# NB2_DBCON.net
KiCad netlist of a schematic drawn in Altium Designer
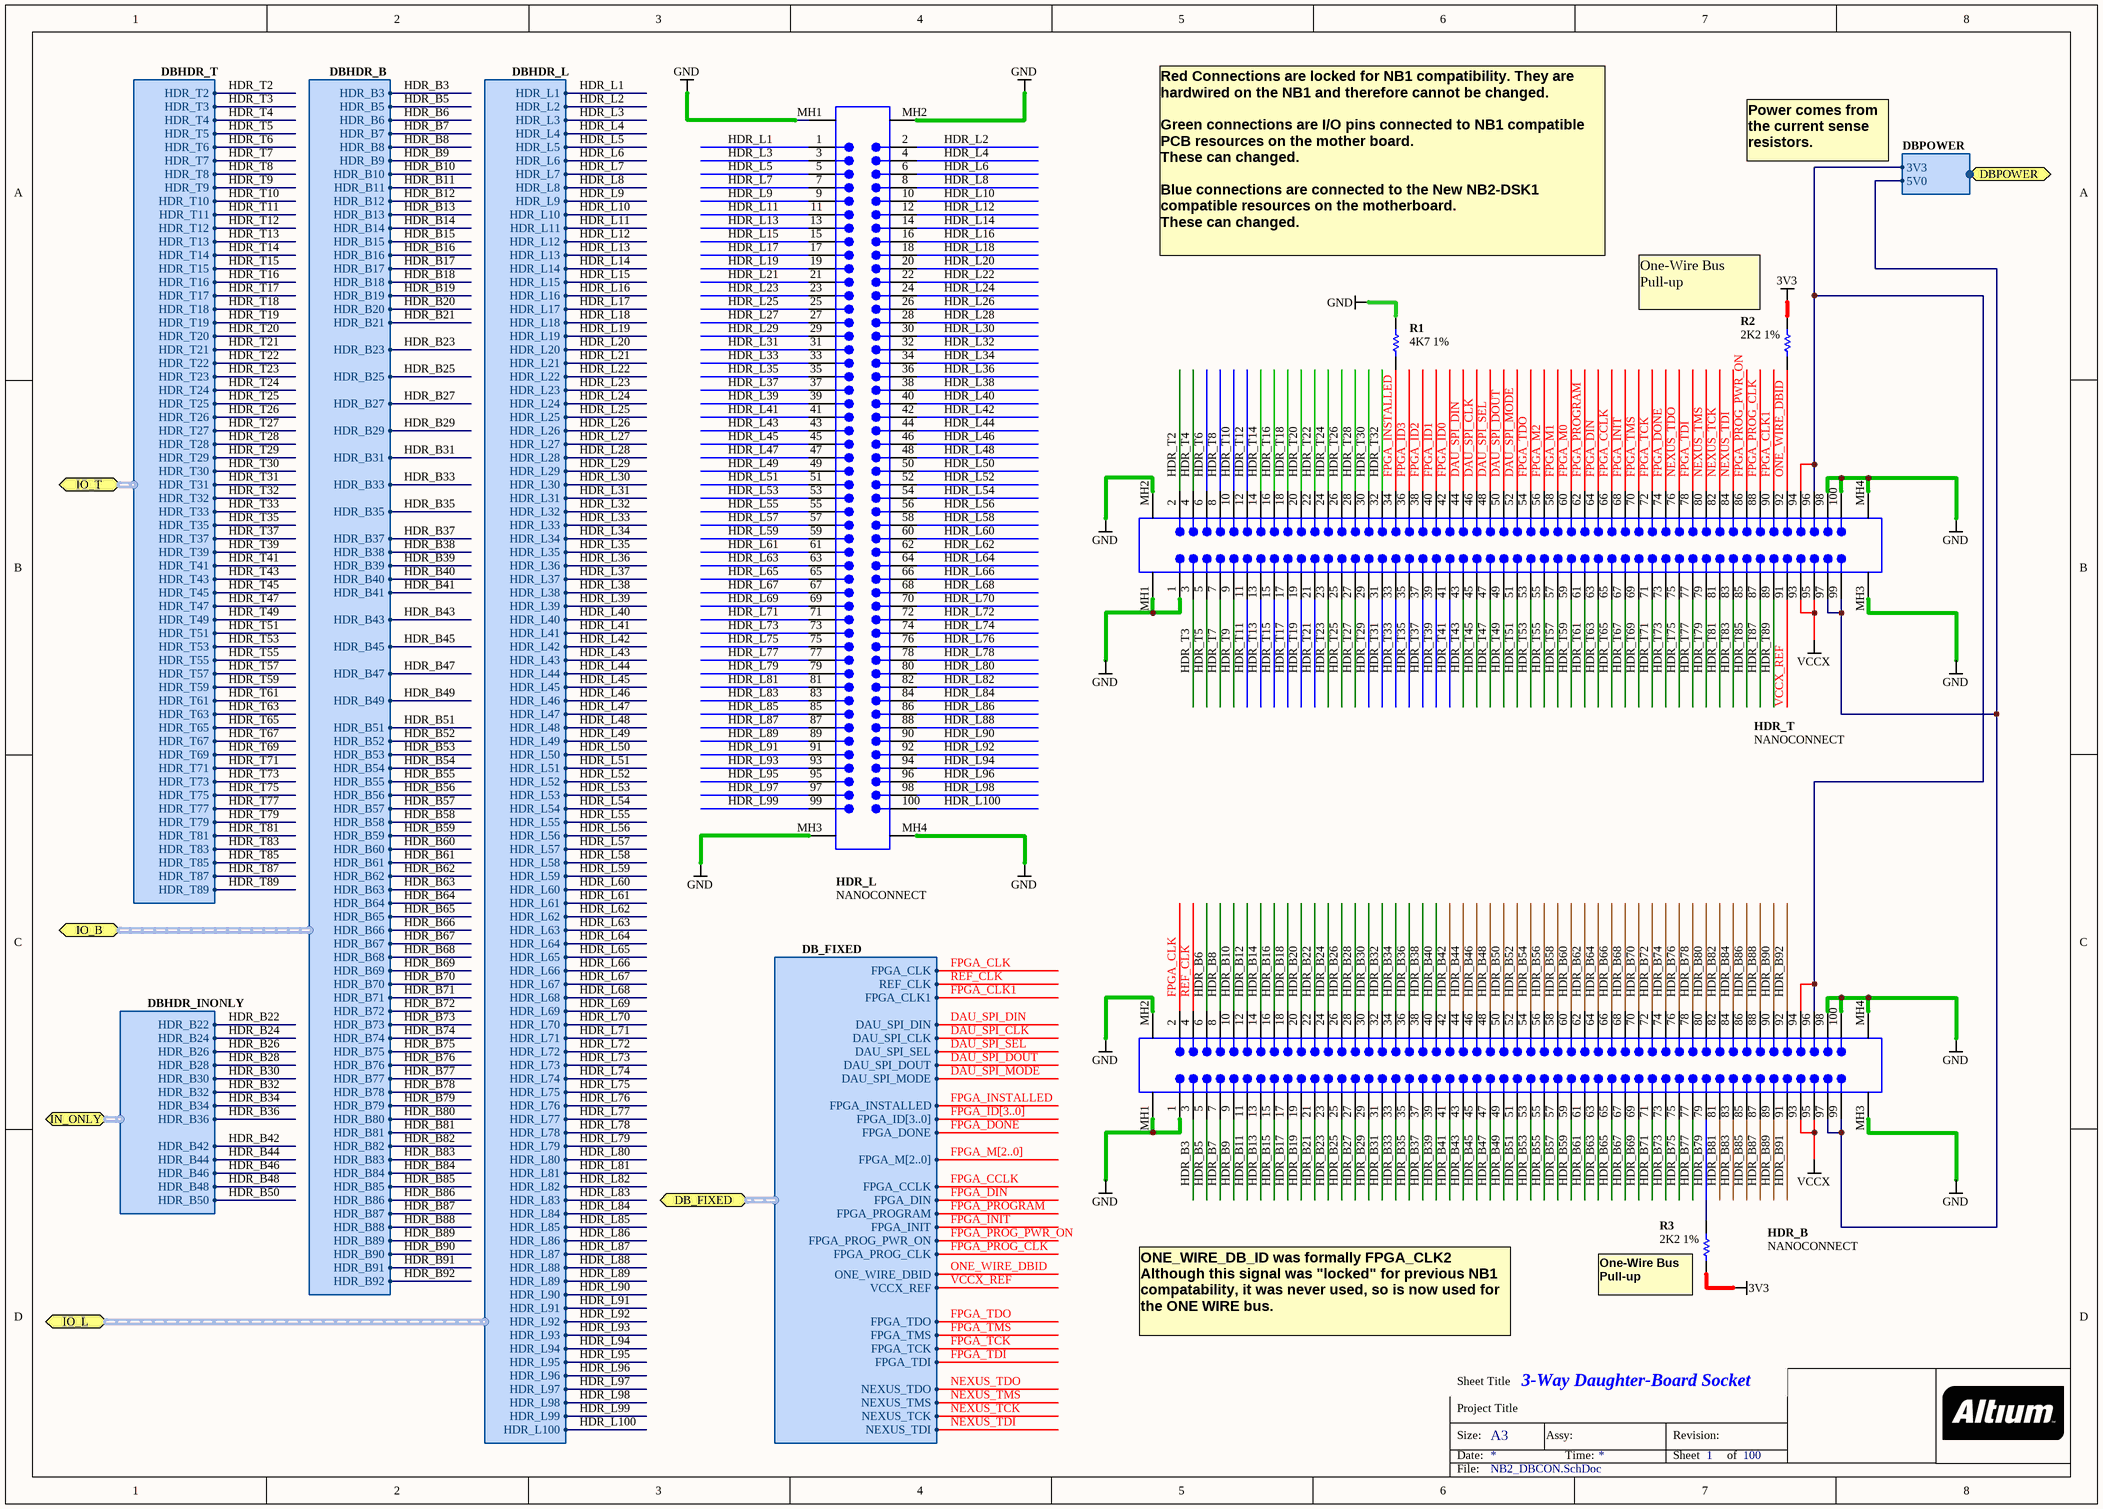
[diagram p0: NB2_DBCON.SchDoc]

(export (version "E")
  (design (tool "Eeschema 10.0.6"))
  (components
    (comp (ref "HDR_B")
      (value "NANOCONNECT")
      (footprint "53751")
      (description "Connector, Molex Docking Station 100 Pin Female 53751")
      (libsource (lib "altium-import") (part "root_1_CON-DOCKSTAT-100-F-STR_"))
    )
    (comp (ref "HDR_L")
      (value "NANOCONNECT")
      (footprint "53751")
      (description "Connector, Molex Docking Station 100 Pin Female 53751")
      (libsource (lib "altium-import") (part "root_0_CON-DOCKSTAT-100-F-STR_"))
    )
    (comp (ref "HDR_T")
      (value "NANOCONNECT")
      (footprint "53751")
      (description "Connector, Molex Docking Station 100 Pin Female 53751")
      (libsource (lib "altium-import") (part "root_1_CON-DOCKSTAT-100-F-STR_"))
    )
    (comp (ref "R1")
      (value "4K7 1%")
      (footprint "RESC1005-STAR")
      (description "Resistor, 4K7 1% 0402 (1005)")
      (fields (field (name "TOLERANCE") "1 %"))
      (libsource (lib "altium-import") (part "root_2_RES_"))
    )
    (comp (ref "R2")
      (value "2K2 1%")
      (footprint "RESC1005-STAR")
      (description "Resistor, 2K2 1% 0402 (1005)")
      (fields (field (name "TOLERANCE") "1 %"))
      (libsource (lib "altium-import") (part "root_2_RES_"))
    )
    (comp (ref "R3")
      (value "2K2 1%")
      (footprint "RESC1005-STAR")
      (description "Resistor, 2K2 1% 0402 (1005)")
      (fields (field (name "TOLERANCE") "1 %"))
      (libsource (lib "altium-import") (part "root_2_RES_"))
    )
  )
  (nets
    (net (code "7") (name "/DAU_SPI_CLK") (class "Default")
      (node (ref "HDR_T") (pin "46") (pinfunction "46_46") (pintype "passive"))
    )
    (net (code "8") (name "/DAU_SPI_DIN") (class "Default")
      (node (ref "HDR_T") (pin "44") (pinfunction "44_44") (pintype "passive"))
    )
    (net (code "9") (name "/DAU_SPI_DOUT") (class "Default")
      (node (ref "HDR_T") (pin "50") (pinfunction "50_50") (pintype "passive"))
    )
    (net (code "10") (name "/DAU_SPI_MODE") (class "Default")
      (node (ref "HDR_T") (pin "52") (pinfunction "52_52") (pintype "passive"))
    )
    (net (code "11") (name "/DAU_SPI_SEL") (class "Default")
      (node (ref "HDR_T") (pin "48") (pinfunction "48_48") (pintype "passive"))
    )
    (net (code "13") (name "/FPGA_CCLK") (class "Default")
      (node (ref "HDR_T") (pin "66") (pinfunction "66_66") (pintype "passive"))
    )
    (net (code "14") (name "/FPGA_CLK") (class "Default")
      (node (ref "HDR_B") (pin "2") (pinfunction "2_2") (pintype "passive"))
    )
    (net (code "15") (name "/FPGA_CLK1") (class "Default")
      (node (ref "HDR_T") (pin "90") (pinfunction "90_90") (pintype "passive"))
    )
    (net (code "16") (name "/FPGA_DIN") (class "Default")
      (node (ref "HDR_T") (pin "64") (pinfunction "64_64") (pintype "passive"))
    )
    (net (code "17") (name "/FPGA_DONE") (class "Default")
      (node (ref "HDR_T") (pin "74") (pinfunction "74_74") (pintype "passive"))
    )
    (net (code "18") (name "/FPGA_ID0") (class "Default")
      (node (ref "HDR_T") (pin "42") (pinfunction "42_42") (pintype "passive"))
    )
    (net (code "19") (name "/FPGA_ID1") (class "Default")
      (node (ref "HDR_T") (pin "40") (pinfunction "40_40") (pintype "passive"))
    )
    (net (code "20") (name "/FPGA_ID2") (class "Default")
      (node (ref "HDR_T") (pin "38") (pinfunction "38_38") (pintype "passive"))
    )
    (net (code "21") (name "/FPGA_ID3") (class "Default")
      (node (ref "HDR_T") (pin "36") (pinfunction "36_36") (pintype "passive"))
    )
    (net (code "23") (name "/FPGA_INIT") (class "Default")
      (node (ref "HDR_T") (pin "68") (pinfunction "68_68") (pintype "passive"))
    )
    (net (code "24") (name "/FPGA_INSTALLED") (class "Default")
      (node (ref "HDR_T") (pin "34") (pinfunction "34_34") (pintype "passive"))
      (node (ref "R1") (pin "1") (pinfunction "1_1") (pintype "passive"))
    )
    (net (code "25") (name "/FPGA_M0") (class "Default")
      (node (ref "HDR_T") (pin "60") (pinfunction "60_60") (pintype "passive"))
    )
    (net (code "26") (name "/FPGA_M1") (class "Default")
      (node (ref "HDR_T") (pin "58") (pinfunction "58_58") (pintype "passive"))
    )
    (net (code "27") (name "/FPGA_M2") (class "Default")
      (node (ref "HDR_T") (pin "56") (pinfunction "56_56") (pintype "passive"))
    )
    (net (code "28") (name "/FPGA_PROGRAM") (class "Default")
      (node (ref "HDR_T") (pin "62") (pinfunction "62_62") (pintype "passive"))
    )
    (net (code "29") (name "/FPGA_PROG_CLK") (class "Default")
      (node (ref "HDR_T") (pin "88") (pinfunction "88_88") (pintype "passive"))
    )
    (net (code "30") (name "/FPGA_PROG_PWR_ON") (class "Default")
      (node (ref "HDR_T") (pin "86") (pinfunction "86_86") (pintype "passive"))
    )
    (net (code "31") (name "/FPGA_TCK") (class "Default")
      (node (ref "HDR_T") (pin "72") (pinfunction "72_72") (pintype "passive"))
    )
    (net (code "32") (name "/FPGA_TDI") (class "Default")
      (node (ref "HDR_T") (pin "78") (pinfunction "78_78") (pintype "passive"))
    )
    (net (code "33") (name "/FPGA_TDO") (class "Default")
      (node (ref "HDR_T") (pin "54") (pinfunction "54_54") (pintype "passive"))
    )
    (net (code "34") (name "/FPGA_TMS") (class "Default")
      (node (ref "HDR_T") (pin "70") (pinfunction "70_70") (pintype "passive"))
    )
    (net (code "35") (name "/HDR_B3") (class "Default")
      (node (ref "HDR_B") (pin "3") (pinfunction "3_3") (pintype "passive"))
    )
    (net (code "36") (name "/HDR_B5") (class "Default")
      (node (ref "HDR_B") (pin "5") (pinfunction "5_5") (pintype "passive"))
    )
    (net (code "37") (name "/HDR_B6") (class "Default")
      (node (ref "HDR_B") (pin "6") (pinfunction "6_6") (pintype "passive"))
    )
    (net (code "38") (name "/HDR_B7") (class "Default")
      (node (ref "HDR_B") (pin "7") (pinfunction "7_7") (pintype "passive"))
    )
    (net (code "39") (name "/HDR_B8") (class "Default")
      (node (ref "HDR_B") (pin "8") (pinfunction "8_8") (pintype "passive"))
    )
    (net (code "40") (name "/HDR_B9") (class "Default")
      (node (ref "HDR_B") (pin "9") (pinfunction "9_9") (pintype "passive"))
    )
    (net (code "41") (name "/HDR_B10") (class "Default")
      (node (ref "HDR_B") (pin "10") (pinfunction "10_10") (pintype "passive"))
    )
    (net (code "42") (name "/HDR_B11") (class "Default")
      (node (ref "HDR_B") (pin "11") (pinfunction "11_11") (pintype "passive"))
    )
    (net (code "43") (name "/HDR_B12") (class "Default")
      (node (ref "HDR_B") (pin "12") (pinfunction "12_12") (pintype "passive"))
    )
    (net (code "44") (name "/HDR_B13") (class "Default")
      (node (ref "HDR_B") (pin "13") (pinfunction "13_13") (pintype "passive"))
    )
    (net (code "45") (name "/HDR_B14") (class "Default")
      (node (ref "HDR_B") (pin "14") (pinfunction "14_14") (pintype "passive"))
    )
    (net (code "46") (name "/HDR_B15") (class "Default")
      (node (ref "HDR_B") (pin "15") (pinfunction "15_15") (pintype "passive"))
    )
    (net (code "47") (name "/HDR_B16") (class "Default")
      (node (ref "HDR_B") (pin "16") (pinfunction "16_16") (pintype "passive"))
    )
    (net (code "48") (name "/HDR_B17") (class "Default")
      (node (ref "HDR_B") (pin "17") (pinfunction "17_17") (pintype "passive"))
    )
    (net (code "49") (name "/HDR_B18") (class "Default")
      (node (ref "HDR_B") (pin "18") (pinfunction "18_18") (pintype "passive"))
    )
    (net (code "50") (name "/HDR_B19") (class "Default")
      (node (ref "HDR_B") (pin "19") (pinfunction "19_19") (pintype "passive"))
    )
    (net (code "51") (name "/HDR_B20") (class "Default")
      (node (ref "HDR_B") (pin "20") (pinfunction "20_20") (pintype "passive"))
    )
    (net (code "52") (name "/HDR_B21") (class "Default")
      (node (ref "HDR_B") (pin "21") (pinfunction "21_21") (pintype "passive"))
    )
    (net (code "53") (name "/HDR_B22") (class "Default")
      (node (ref "HDR_B") (pin "22") (pinfunction "22_22") (pintype "passive"))
    )
    (net (code "54") (name "/HDR_B23") (class "Default")
      (node (ref "HDR_B") (pin "23") (pinfunction "23_23") (pintype "passive"))
    )
    (net (code "55") (name "/HDR_B24") (class "Default")
      (node (ref "HDR_B") (pin "24") (pinfunction "24_24") (pintype "passive"))
    )
    (net (code "56") (name "/HDR_B25") (class "Default")
      (node (ref "HDR_B") (pin "25") (pinfunction "25_25") (pintype "passive"))
    )
    (net (code "57") (name "/HDR_B26") (class "Default")
      (node (ref "HDR_B") (pin "26") (pinfunction "26_26") (pintype "passive"))
    )
    (net (code "58") (name "/HDR_B27") (class "Default")
      (node (ref "HDR_B") (pin "27") (pinfunction "27_27") (pintype "passive"))
    )
    (net (code "59") (name "/HDR_B28") (class "Default")
      (node (ref "HDR_B") (pin "28") (pinfunction "28_28") (pintype "passive"))
    )
    (net (code "60") (name "/HDR_B29") (class "Default")
      (node (ref "HDR_B") (pin "29") (pinfunction "29_29") (pintype "passive"))
    )
    (net (code "61") (name "/HDR_B30") (class "Default")
      (node (ref "HDR_B") (pin "30") (pinfunction "30_30") (pintype "passive"))
    )
    (net (code "62") (name "/HDR_B31") (class "Default")
      (node (ref "HDR_B") (pin "31") (pinfunction "31_31") (pintype "passive"))
    )
    (net (code "63") (name "/HDR_B32") (class "Default")
      (node (ref "HDR_B") (pin "32") (pinfunction "32_32") (pintype "passive"))
    )
    (net (code "64") (name "/HDR_B33") (class "Default")
      (node (ref "HDR_B") (pin "33") (pinfunction "33_33") (pintype "passive"))
    )
    (net (code "65") (name "/HDR_B34") (class "Default")
      (node (ref "HDR_B") (pin "34") (pinfunction "34_34") (pintype "passive"))
    )
    (net (code "66") (name "/HDR_B35") (class "Default")
      (node (ref "HDR_B") (pin "35") (pinfunction "35_35") (pintype "passive"))
    )
    (net (code "67") (name "/HDR_B36") (class "Default")
      (node (ref "HDR_B") (pin "36") (pinfunction "36_36") (pintype "passive"))
    )
    (net (code "68") (name "/HDR_B37") (class "Default")
      (node (ref "HDR_B") (pin "37") (pinfunction "37_37") (pintype "passive"))
    )
    (net (code "69") (name "/HDR_B38") (class "Default")
      (node (ref "HDR_B") (pin "38") (pinfunction "38_38") (pintype "passive"))
    )
    (net (code "70") (name "/HDR_B39") (class "Default")
      (node (ref "HDR_B") (pin "39") (pinfunction "39_39") (pintype "passive"))
    )
    (net (code "71") (name "/HDR_B40") (class "Default")
      (node (ref "HDR_B") (pin "40") (pinfunction "40_40") (pintype "passive"))
    )
    (net (code "72") (name "/HDR_B41") (class "Default")
      (node (ref "HDR_B") (pin "41") (pinfunction "41_41") (pintype "passive"))
    )
    (net (code "73") (name "/HDR_B42") (class "Default")
      (node (ref "HDR_B") (pin "42") (pinfunction "42_42") (pintype "passive"))
    )
    (net (code "74") (name "/HDR_B43") (class "Default")
      (node (ref "HDR_B") (pin "43") (pinfunction "43_43") (pintype "passive"))
    )
    (net (code "75") (name "/HDR_B44") (class "Default")
      (node (ref "HDR_B") (pin "44") (pinfunction "44_44") (pintype "passive"))
    )
    (net (code "76") (name "/HDR_B45") (class "Default")
      (node (ref "HDR_B") (pin "45") (pinfunction "45_45") (pintype "passive"))
    )
    (net (code "77") (name "/HDR_B46") (class "Default")
      (node (ref "HDR_B") (pin "46") (pinfunction "46_46") (pintype "passive"))
    )
    (net (code "78") (name "/HDR_B47") (class "Default")
      (node (ref "HDR_B") (pin "47") (pinfunction "47_47") (pintype "passive"))
    )
    (net (code "79") (name "/HDR_B48") (class "Default")
      (node (ref "HDR_B") (pin "48") (pinfunction "48_48") (pintype "passive"))
    )
    (net (code "80") (name "/HDR_B49") (class "Default")
      (node (ref "HDR_B") (pin "49") (pinfunction "49_49") (pintype "passive"))
    )
    (net (code "81") (name "/HDR_B50") (class "Default")
      (node (ref "HDR_B") (pin "50") (pinfunction "50_50") (pintype "passive"))
    )
    (net (code "82") (name "/HDR_B51") (class "Default")
      (node (ref "HDR_B") (pin "51") (pinfunction "51_51") (pintype "passive"))
    )
    (net (code "83") (name "/HDR_B52") (class "Default")
      (node (ref "HDR_B") (pin "52") (pinfunction "52_52") (pintype "passive"))
    )
    (net (code "84") (name "/HDR_B53") (class "Default")
      (node (ref "HDR_B") (pin "53") (pinfunction "53_53") (pintype "passive"))
    )
    (net (code "85") (name "/HDR_B54") (class "Default")
      (node (ref "HDR_B") (pin "54") (pinfunction "54_54") (pintype "passive"))
    )
    (net (code "86") (name "/HDR_B55") (class "Default")
      (node (ref "HDR_B") (pin "55") (pinfunction "55_55") (pintype "passive"))
    )
    (net (code "87") (name "/HDR_B56") (class "Default")
      (node (ref "HDR_B") (pin "56") (pinfunction "56_56") (pintype "passive"))
    )
    (net (code "88") (name "/HDR_B57") (class "Default")
      (node (ref "HDR_B") (pin "57") (pinfunction "57_57") (pintype "passive"))
    )
    (net (code "89") (name "/HDR_B58") (class "Default")
      (node (ref "HDR_B") (pin "58") (pinfunction "58_58") (pintype "passive"))
    )
    (net (code "90") (name "/HDR_B59") (class "Default")
      (node (ref "HDR_B") (pin "59") (pinfunction "59_59") (pintype "passive"))
    )
    (net (code "91") (name "/HDR_B60") (class "Default")
      (node (ref "HDR_B") (pin "60") (pinfunction "60_60") (pintype "passive"))
    )
    (net (code "92") (name "/HDR_B61") (class "Default")
      (node (ref "HDR_B") (pin "61") (pinfunction "61_61") (pintype "passive"))
    )
    (net (code "93") (name "/HDR_B62") (class "Default")
      (node (ref "HDR_B") (pin "62") (pinfunction "62_62") (pintype "passive"))
    )
    (net (code "94") (name "/HDR_B63") (class "Default")
      (node (ref "HDR_B") (pin "63") (pinfunction "63_63") (pintype "passive"))
    )
    (net (code "95") (name "/HDR_B64") (class "Default")
      (node (ref "HDR_B") (pin "64") (pinfunction "64_64") (pintype "passive"))
    )
    (net (code "96") (name "/HDR_B65") (class "Default")
      (node (ref "HDR_B") (pin "65") (pinfunction "65_65") (pintype "passive"))
    )
    (net (code "97") (name "/HDR_B66") (class "Default")
      (node (ref "HDR_B") (pin "66") (pinfunction "66_66") (pintype "passive"))
    )
    (net (code "98") (name "/HDR_B67") (class "Default")
      (node (ref "HDR_B") (pin "67") (pinfunction "67_67") (pintype "passive"))
    )
    (net (code "99") (name "/HDR_B68") (class "Default")
      (node (ref "HDR_B") (pin "68") (pinfunction "68_68") (pintype "passive"))
    )
    (net (code "100") (name "/HDR_B69") (class "Default")
      (node (ref "HDR_B") (pin "69") (pinfunction "69_69") (pintype "passive"))
    )
    (net (code "101") (name "/HDR_B70") (class "Default")
      (node (ref "HDR_B") (pin "70") (pinfunction "70_70") (pintype "passive"))
    )
    (net (code "102") (name "/HDR_B71") (class "Default")
      (node (ref "HDR_B") (pin "71") (pinfunction "71_71") (pintype "passive"))
    )
    (net (code "103") (name "/HDR_B72") (class "Default")
      (node (ref "HDR_B") (pin "72") (pinfunction "72_72") (pintype "passive"))
    )
    (net (code "104") (name "/HDR_B73") (class "Default")
      (node (ref "HDR_B") (pin "73") (pinfunction "73_73") (pintype "passive"))
    )
    (net (code "105") (name "/HDR_B74") (class "Default")
      (node (ref "HDR_B") (pin "74") (pinfunction "74_74") (pintype "passive"))
    )
    (net (code "106") (name "/HDR_B75") (class "Default")
      (node (ref "HDR_B") (pin "75") (pinfunction "75_75") (pintype "passive"))
    )
    (net (code "107") (name "/HDR_B76") (class "Default")
      (node (ref "HDR_B") (pin "76") (pinfunction "76_76") (pintype "passive"))
    )
    (net (code "108") (name "/HDR_B77") (class "Default")
      (node (ref "HDR_B") (pin "77") (pinfunction "77_77") (pintype "passive"))
    )
    (net (code "109") (name "/HDR_B78") (class "Default")
      (node (ref "HDR_B") (pin "78") (pinfunction "78_78") (pintype "passive"))
    )
    (net (code "110") (name "/HDR_B79") (class "Default")
      (node (ref "HDR_B") (pin "79") (pinfunction "79_79") (pintype "passive"))
      (node (ref "R3") (pin "2") (pinfunction "2_2") (pintype "passive"))
    )
    (net (code "111") (name "/HDR_B80") (class "Default")
      (node (ref "HDR_B") (pin "80") (pinfunction "80_80") (pintype "passive"))
    )
    (net (code "112") (name "/HDR_B81") (class "Default")
      (node (ref "HDR_B") (pin "81") (pinfunction "81_81") (pintype "passive"))
    )
    (net (code "113") (name "/HDR_B82") (class "Default")
      (node (ref "HDR_B") (pin "82") (pinfunction "82_82") (pintype "passive"))
    )
    (net (code "114") (name "/HDR_B83") (class "Default")
      (node (ref "HDR_B") (pin "83") (pinfunction "83_83") (pintype "passive"))
    )
    (net (code "115") (name "/HDR_B84") (class "Default")
      (node (ref "HDR_B") (pin "84") (pinfunction "84_84") (pintype "passive"))
    )
    (net (code "116") (name "/HDR_B85") (class "Default")
      (node (ref "HDR_B") (pin "85") (pinfunction "85_85") (pintype "passive"))
    )
    (net (code "117") (name "/HDR_B86") (class "Default")
      (node (ref "HDR_B") (pin "86") (pinfunction "86_86") (pintype "passive"))
    )
    (net (code "118") (name "/HDR_B87") (class "Default")
      (node (ref "HDR_B") (pin "87") (pinfunction "87_87") (pintype "passive"))
    )
    (net (code "119") (name "/HDR_B88") (class "Default")
      (node (ref "HDR_B") (pin "88") (pinfunction "88_88") (pintype "passive"))
    )
    (net (code "120") (name "/HDR_B89") (class "Default")
      (node (ref "HDR_B") (pin "89") (pinfunction "89_89") (pintype "passive"))
    )
    (net (code "121") (name "/HDR_B90") (class "Default")
      (node (ref "HDR_B") (pin "90") (pinfunction "90_90") (pintype "passive"))
    )
    (net (code "122") (name "/HDR_B91") (class "Default")
      (node (ref "HDR_B") (pin "91") (pinfunction "91_91") (pintype "passive"))
    )
    (net (code "123") (name "/HDR_B92") (class "Default")
      (node (ref "HDR_B") (pin "92") (pinfunction "92_92") (pintype "passive"))
    )
    (net (code "124") (name "/HDR_L1") (class "Default")
      (node (ref "HDR_L") (pin "1") (pinfunction "1_1") (pintype "passive"))
    )
    (net (code "125") (name "/HDR_L2") (class "Default")
      (node (ref "HDR_L") (pin "2") (pinfunction "2_2") (pintype "passive"))
    )
    (net (code "126") (name "/HDR_L3") (class "Default")
      (node (ref "HDR_L") (pin "3") (pinfunction "3_3") (pintype "passive"))
    )
    (net (code "127") (name "/HDR_L4") (class "Default")
      (node (ref "HDR_L") (pin "4") (pinfunction "4_4") (pintype "passive"))
    )
    (net (code "128") (name "/HDR_L5") (class "Default")
      (node (ref "HDR_L") (pin "5") (pinfunction "5_5") (pintype "passive"))
    )
    (net (code "129") (name "/HDR_L6") (class "Default")
      (node (ref "HDR_L") (pin "6") (pinfunction "6_6") (pintype "passive"))
    )
    (net (code "130") (name "/HDR_L7") (class "Default")
      (node (ref "HDR_L") (pin "7") (pinfunction "7_7") (pintype "passive"))
    )
    (net (code "131") (name "/HDR_L8") (class "Default")
      (node (ref "HDR_L") (pin "8") (pinfunction "8_8") (pintype "passive"))
    )
    (net (code "132") (name "/HDR_L9") (class "Default")
      (node (ref "HDR_L") (pin "9") (pinfunction "9_9") (pintype "passive"))
    )
    (net (code "133") (name "/HDR_L10") (class "Default")
      (node (ref "HDR_L") (pin "10") (pinfunction "10_10") (pintype "passive"))
    )
    (net (code "134") (name "/HDR_L11") (class "Default")
      (node (ref "HDR_L") (pin "11") (pinfunction "11_11") (pintype "passive"))
    )
    (net (code "135") (name "/HDR_L12") (class "Default")
      (node (ref "HDR_L") (pin "12") (pinfunction "12_12") (pintype "passive"))
    )
    (net (code "136") (name "/HDR_L13") (class "Default")
      (node (ref "HDR_L") (pin "13") (pinfunction "13_13") (pintype "passive"))
    )
    (net (code "137") (name "/HDR_L14") (class "Default")
      (node (ref "HDR_L") (pin "14") (pinfunction "14_14") (pintype "passive"))
    )
    (net (code "138") (name "/HDR_L15") (class "Default")
      (node (ref "HDR_L") (pin "15") (pinfunction "15_15") (pintype "passive"))
    )
    (net (code "139") (name "/HDR_L16") (class "Default")
      (node (ref "HDR_L") (pin "16") (pinfunction "16_16") (pintype "passive"))
    )
    (net (code "140") (name "/HDR_L17") (class "Default")
      (node (ref "HDR_L") (pin "17") (pinfunction "17_17") (pintype "passive"))
    )
    (net (code "141") (name "/HDR_L18") (class "Default")
      (node (ref "HDR_L") (pin "18") (pinfunction "18_18") (pintype "passive"))
    )
    (net (code "142") (name "/HDR_L19") (class "Default")
      (node (ref "HDR_L") (pin "19") (pinfunction "19_19") (pintype "passive"))
    )
    (net (code "143") (name "/HDR_L20") (class "Default")
      (node (ref "HDR_L") (pin "20") (pinfunction "20_20") (pintype "passive"))
    )
    (net (code "144") (name "/HDR_L21") (class "Default")
      (node (ref "HDR_L") (pin "21") (pinfunction "21_21") (pintype "passive"))
    )
    (net (code "145") (name "/HDR_L22") (class "Default")
      (node (ref "HDR_L") (pin "22") (pinfunction "22_22") (pintype "passive"))
    )
    (net (code "146") (name "/HDR_L23") (class "Default")
      (node (ref "HDR_L") (pin "23") (pinfunction "23_23") (pintype "passive"))
    )
    (net (code "147") (name "/HDR_L24") (class "Default")
      (node (ref "HDR_L") (pin "24") (pinfunction "24_24") (pintype "passive"))
    )
    (net (code "148") (name "/HDR_L25") (class "Default")
      (node (ref "HDR_L") (pin "25") (pinfunction "25_25") (pintype "passive"))
    )
    (net (code "149") (name "/HDR_L26") (class "Default")
      (node (ref "HDR_L") (pin "26") (pinfunction "26_26") (pintype "passive"))
    )
    (net (code "150") (name "/HDR_L27") (class "Default")
      (node (ref "HDR_L") (pin "27") (pinfunction "27_27") (pintype "passive"))
    )
    (net (code "151") (name "/HDR_L28") (class "Default")
      (node (ref "HDR_L") (pin "28") (pinfunction "28_28") (pintype "passive"))
    )
    (net (code "152") (name "/HDR_L29") (class "Default")
      (node (ref "HDR_L") (pin "29") (pinfunction "29_29") (pintype "passive"))
    )
    (net (code "153") (name "/HDR_L30") (class "Default")
      (node (ref "HDR_L") (pin "30") (pinfunction "30_30") (pintype "passive"))
    )
    (net (code "154") (name "/HDR_L31") (class "Default")
      (node (ref "HDR_L") (pin "31") (pinfunction "31_31") (pintype "passive"))
    )
    (net (code "155") (name "/HDR_L32") (class "Default")
      (node (ref "HDR_L") (pin "32") (pinfunction "32_32") (pintype "passive"))
    )
    (net (code "156") (name "/HDR_L33") (class "Default")
      (node (ref "HDR_L") (pin "33") (pinfunction "33_33") (pintype "passive"))
    )
    (net (code "157") (name "/HDR_L34") (class "Default")
      (node (ref "HDR_L") (pin "34") (pinfunction "34_34") (pintype "passive"))
    )
    (net (code "158") (name "/HDR_L35") (class "Default")
      (node (ref "HDR_L") (pin "35") (pinfunction "35_35") (pintype "passive"))
    )
    (net (code "159") (name "/HDR_L36") (class "Default")
      (node (ref "HDR_L") (pin "36") (pinfunction "36_36") (pintype "passive"))
    )
    (net (code "160") (name "/HDR_L37") (class "Default")
      (node (ref "HDR_L") (pin "37") (pinfunction "37_37") (pintype "passive"))
    )
    (net (code "161") (name "/HDR_L38") (class "Default")
      (node (ref "HDR_L") (pin "38") (pinfunction "38_38") (pintype "passive"))
    )
    (net (code "162") (name "/HDR_L39") (class "Default")
      (node (ref "HDR_L") (pin "39") (pinfunction "39_39") (pintype "passive"))
    )
    (net (code "163") (name "/HDR_L40") (class "Default")
      (node (ref "HDR_L") (pin "40") (pinfunction "40_40") (pintype "passive"))
    )
    (net (code "164") (name "/HDR_L41") (class "Default")
      (node (ref "HDR_L") (pin "41") (pinfunction "41_41") (pintype "passive"))
    )
    (net (code "165") (name "/HDR_L42") (class "Default")
      (node (ref "HDR_L") (pin "42") (pinfunction "42_42") (pintype "passive"))
    )
    (net (code "166") (name "/HDR_L43") (class "Default")
      (node (ref "HDR_L") (pin "43") (pinfunction "43_43") (pintype "passive"))
    )
    (net (code "167") (name "/HDR_L44") (class "Default")
      (node (ref "HDR_L") (pin "44") (pinfunction "44_44") (pintype "passive"))
    )
    (net (code "168") (name "/HDR_L45") (class "Default")
      (node (ref "HDR_L") (pin "45") (pinfunction "45_45") (pintype "passive"))
    )
    (net (code "169") (name "/HDR_L46") (class "Default")
      (node (ref "HDR_L") (pin "46") (pinfunction "46_46") (pintype "passive"))
    )
    (net (code "170") (name "/HDR_L47") (class "Default")
      (node (ref "HDR_L") (pin "47") (pinfunction "47_47") (pintype "passive"))
    )
    (net (code "171") (name "/HDR_L48") (class "Default")
      (node (ref "HDR_L") (pin "48") (pinfunction "48_48") (pintype "passive"))
    )
    (net (code "172") (name "/HDR_L49") (class "Default")
      (node (ref "HDR_L") (pin "49") (pinfunction "49_49") (pintype "passive"))
    )
    (net (code "173") (name "/HDR_L50") (class "Default")
      (node (ref "HDR_L") (pin "50") (pinfunction "50_50") (pintype "passive"))
    )
    (net (code "174") (name "/HDR_L51") (class "Default")
      (node (ref "HDR_L") (pin "51") (pinfunction "51_51") (pintype "passive"))
    )
    (net (code "175") (name "/HDR_L52") (class "Default")
      (node (ref "HDR_L") (pin "52") (pinfunction "52_52") (pintype "passive"))
    )
    (net (code "176") (name "/HDR_L53") (class "Default")
      (node (ref "HDR_L") (pin "53") (pinfunction "53_53") (pintype "passive"))
    )
    (net (code "177") (name "/HDR_L54") (class "Default")
      (node (ref "HDR_L") (pin "54") (pinfunction "54_54") (pintype "passive"))
    )
    (net (code "178") (name "/HDR_L55") (class "Default")
      (node (ref "HDR_L") (pin "55") (pinfunction "55_55") (pintype "passive"))
    )
    (net (code "179") (name "/HDR_L56") (class "Default")
      (node (ref "HDR_L") (pin "56") (pinfunction "56_56") (pintype "passive"))
    )
    (net (code "180") (name "/HDR_L57") (class "Default")
      (node (ref "HDR_L") (pin "57") (pinfunction "57_57") (pintype "passive"))
    )
    (net (code "181") (name "/HDR_L58") (class "Default")
      (node (ref "HDR_L") (pin "58") (pinfunction "58_58") (pintype "passive"))
    )
    (net (code "182") (name "/HDR_L59") (class "Default")
      (node (ref "HDR_L") (pin "59") (pinfunction "59_59") (pintype "passive"))
    )
    (net (code "183") (name "/HDR_L60") (class "Default")
      (node (ref "HDR_L") (pin "60") (pinfunction "60_60") (pintype "passive"))
    )
    (net (code "184") (name "/HDR_L61") (class "Default")
      (node (ref "HDR_L") (pin "61") (pinfunction "61_61") (pintype "passive"))
    )
    (net (code "185") (name "/HDR_L62") (class "Default")
      (node (ref "HDR_L") (pin "62") (pinfunction "62_62") (pintype "passive"))
    )
    (net (code "186") (name "/HDR_L63") (class "Default")
      (node (ref "HDR_L") (pin "63") (pinfunction "63_63") (pintype "passive"))
    )
    (net (code "187") (name "/HDR_L64") (class "Default")
      (node (ref "HDR_L") (pin "64") (pinfunction "64_64") (pintype "passive"))
    )
    (net (code "188") (name "/HDR_L65") (class "Default")
      (node (ref "HDR_L") (pin "65") (pinfunction "65_65") (pintype "passive"))
    )
    (net (code "189") (name "/HDR_L66") (class "Default")
      (node (ref "HDR_L") (pin "66") (pinfunction "66_66") (pintype "passive"))
    )
    (net (code "190") (name "/HDR_L67") (class "Default")
      (node (ref "HDR_L") (pin "67") (pinfunction "67_67") (pintype "passive"))
    )
    (net (code "191") (name "/HDR_L68") (class "Default")
      (node (ref "HDR_L") (pin "68") (pinfunction "68_68") (pintype "passive"))
    )
    (net (code "192") (name "/HDR_L69") (class "Default")
      (node (ref "HDR_L") (pin "69") (pinfunction "69_69") (pintype "passive"))
    )
    (net (code "193") (name "/HDR_L70") (class "Default")
      (node (ref "HDR_L") (pin "70") (pinfunction "70_70") (pintype "passive"))
    )
    (net (code "194") (name "/HDR_L71") (class "Default")
      (node (ref "HDR_L") (pin "71") (pinfunction "71_71") (pintype "passive"))
    )
    (net (code "195") (name "/HDR_L72") (class "Default")
      (node (ref "HDR_L") (pin "72") (pinfunction "72_72") (pintype "passive"))
    )
    (net (code "196") (name "/HDR_L73") (class "Default")
      (node (ref "HDR_L") (pin "73") (pinfunction "73_73") (pintype "passive"))
    )
    (net (code "197") (name "/HDR_L74") (class "Default")
      (node (ref "HDR_L") (pin "74") (pinfunction "74_74") (pintype "passive"))
    )
    (net (code "198") (name "/HDR_L75") (class "Default")
      (node (ref "HDR_L") (pin "75") (pinfunction "75_75") (pintype "passive"))
    )
    (net (code "199") (name "/HDR_L76") (class "Default")
      (node (ref "HDR_L") (pin "76") (pinfunction "76_76") (pintype "passive"))
    )
    (net (code "200") (name "/HDR_L77") (class "Default")
      (node (ref "HDR_L") (pin "77") (pinfunction "77_77") (pintype "passive"))
    )
    (net (code "201") (name "/HDR_L78") (class "Default")
      (node (ref "HDR_L") (pin "78") (pinfunction "78_78") (pintype "passive"))
    )
    (net (code "202") (name "/HDR_L79") (class "Default")
      (node (ref "HDR_L") (pin "79") (pinfunction "79_79") (pintype "passive"))
    )
    (net (code "203") (name "/HDR_L80") (class "Default")
      (node (ref "HDR_L") (pin "80") (pinfunction "80_80") (pintype "passive"))
    )
    (net (code "204") (name "/HDR_L81") (class "Default")
      (node (ref "HDR_L") (pin "81") (pinfunction "81_81") (pintype "passive"))
    )
    (net (code "205") (name "/HDR_L82") (class "Default")
      (node (ref "HDR_L") (pin "82") (pinfunction "82_82") (pintype "passive"))
    )
    (net (code "206") (name "/HDR_L83") (class "Default")
      (node (ref "HDR_L") (pin "83") (pinfunction "83_83") (pintype "passive"))
    )
    (net (code "207") (name "/HDR_L84") (class "Default")
      (node (ref "HDR_L") (pin "84") (pinfunction "84_84") (pintype "passive"))
    )
    (net (code "208") (name "/HDR_L85") (class "Default")
      (node (ref "HDR_L") (pin "85") (pinfunction "85_85") (pintype "passive"))
    )
    (net (code "209") (name "/HDR_L86") (class "Default")
      (node (ref "HDR_L") (pin "86") (pinfunction "86_86") (pintype "passive"))
    )
    (net (code "210") (name "/HDR_L87") (class "Default")
      (node (ref "HDR_L") (pin "87") (pinfunction "87_87") (pintype "passive"))
    )
    (net (code "211") (name "/HDR_L88") (class "Default")
      (node (ref "HDR_L") (pin "88") (pinfunction "88_88") (pintype "passive"))
    )
    (net (code "212") (name "/HDR_L89") (class "Default")
      (node (ref "HDR_L") (pin "89") (pinfunction "89_89") (pintype "passive"))
    )
    (net (code "213") (name "/HDR_L90") (class "Default")
      (node (ref "HDR_L") (pin "90") (pinfunction "90_90") (pintype "passive"))
    )
    (net (code "214") (name "/HDR_L91") (class "Default")
      (node (ref "HDR_L") (pin "91") (pinfunction "91_91") (pintype "passive"))
    )
    (net (code "215") (name "/HDR_L92") (class "Default")
      (node (ref "HDR_L") (pin "92") (pinfunction "92_92") (pintype "passive"))
    )
    (net (code "216") (name "/HDR_L93") (class "Default")
      (node (ref "HDR_L") (pin "93") (pinfunction "93_93") (pintype "passive"))
    )
    (net (code "217") (name "/HDR_L94") (class "Default")
      (node (ref "HDR_L") (pin "94") (pinfunction "94_94") (pintype "passive"))
    )
    (net (code "218") (name "/HDR_L95") (class "Default")
      (node (ref "HDR_L") (pin "95") (pinfunction "95_95") (pintype "passive"))
    )
    (net (code "219") (name "/HDR_L96") (class "Default")
      (node (ref "HDR_L") (pin "96") (pinfunction "96_96") (pintype "passive"))
    )
    (net (code "220") (name "/HDR_L97") (class "Default")
      (node (ref "HDR_L") (pin "97") (pinfunction "97_97") (pintype "passive"))
    )
    (net (code "221") (name "/HDR_L98") (class "Default")
      (node (ref "HDR_L") (pin "98") (pinfunction "98_98") (pintype "passive"))
    )
    (net (code "222") (name "/HDR_L99") (class "Default")
      (node (ref "HDR_L") (pin "99") (pinfunction "99_99") (pintype "passive"))
    )
    (net (code "223") (name "/HDR_L100") (class "Default")
      (node (ref "HDR_L") (pin "100") (pinfunction "100_100") (pintype "passive"))
    )
    (net (code "224") (name "/HDR_T2") (class "Default")
      (node (ref "HDR_T") (pin "2") (pinfunction "2_2") (pintype "passive"))
    )
    (net (code "225") (name "/HDR_T3") (class "Default")
      (node (ref "HDR_T") (pin "3") (pinfunction "3_3") (pintype "passive"))
    )
    (net (code "226") (name "/HDR_T4") (class "Default")
      (node (ref "HDR_T") (pin "4") (pinfunction "4_4") (pintype "passive"))
    )
    (net (code "227") (name "/HDR_T5") (class "Default")
      (node (ref "HDR_T") (pin "5") (pinfunction "5_5") (pintype "passive"))
    )
    (net (code "228") (name "/HDR_T6") (class "Default")
      (node (ref "HDR_T") (pin "6") (pinfunction "6_6") (pintype "passive"))
    )
    (net (code "229") (name "/HDR_T7") (class "Default")
      (node (ref "HDR_T") (pin "7") (pinfunction "7_7") (pintype "passive"))
    )
    (net (code "230") (name "/HDR_T8") (class "Default")
      (node (ref "HDR_T") (pin "8") (pinfunction "8_8") (pintype "passive"))
    )
    (net (code "231") (name "/HDR_T9") (class "Default")
      (node (ref "HDR_T") (pin "9") (pinfunction "9_9") (pintype "passive"))
    )
    (net (code "232") (name "/HDR_T10") (class "Default")
      (node (ref "HDR_T") (pin "10") (pinfunction "10_10") (pintype "passive"))
    )
    (net (code "233") (name "/HDR_T11") (class "Default")
      (node (ref "HDR_T") (pin "11") (pinfunction "11_11") (pintype "passive"))
    )
    (net (code "234") (name "/HDR_T12") (class "Default")
      (node (ref "HDR_T") (pin "12") (pinfunction "12_12") (pintype "passive"))
    )
    (net (code "235") (name "/HDR_T13") (class "Default")
      (node (ref "HDR_T") (pin "13") (pinfunction "13_13") (pintype "passive"))
    )
    (net (code "236") (name "/HDR_T14") (class "Default")
      (node (ref "HDR_T") (pin "14") (pinfunction "14_14") (pintype "passive"))
    )
    (net (code "237") (name "/HDR_T15") (class "Default")
      (node (ref "HDR_T") (pin "15") (pinfunction "15_15") (pintype "passive"))
    )
    (net (code "238") (name "/HDR_T16") (class "Default")
      (node (ref "HDR_T") (pin "16") (pinfunction "16_16") (pintype "passive"))
    )
    (net (code "239") (name "/HDR_T17") (class "Default")
      (node (ref "HDR_T") (pin "17") (pinfunction "17_17") (pintype "passive"))
    )
    (net (code "240") (name "/HDR_T18") (class "Default")
      (node (ref "HDR_T") (pin "18") (pinfunction "18_18") (pintype "passive"))
    )
    (net (code "241") (name "/HDR_T19") (class "Default")
      (node (ref "HDR_T") (pin "19") (pinfunction "19_19") (pintype "passive"))
    )
    (net (code "242") (name "/HDR_T20") (class "Default")
      (node (ref "HDR_T") (pin "20") (pinfunction "20_20") (pintype "passive"))
    )
    (net (code "243") (name "/HDR_T21") (class "Default")
      (node (ref "HDR_T") (pin "21") (pinfunction "21_21") (pintype "passive"))
    )
    (net (code "244") (name "/HDR_T22") (class "Default")
      (node (ref "HDR_T") (pin "22") (pinfunction "22_22") (pintype "passive"))
    )
    (net (code "245") (name "/HDR_T23") (class "Default")
      (node (ref "HDR_T") (pin "23") (pinfunction "23_23") (pintype "passive"))
    )
    (net (code "246") (name "/HDR_T24") (class "Default")
      (node (ref "HDR_T") (pin "24") (pinfunction "24_24") (pintype "passive"))
    )
    (net (code "247") (name "/HDR_T25") (class "Default")
      (node (ref "HDR_T") (pin "25") (pinfunction "25_25") (pintype "passive"))
    )
    (net (code "248") (name "/HDR_T26") (class "Default")
      (node (ref "HDR_T") (pin "26") (pinfunction "26_26") (pintype "passive"))
    )
    (net (code "249") (name "/HDR_T27") (class "Default")
      (node (ref "HDR_T") (pin "27") (pinfunction "27_27") (pintype "passive"))
    )
    (net (code "250") (name "/HDR_T28") (class "Default")
      (node (ref "HDR_T") (pin "28") (pinfunction "28_28") (pintype "passive"))
    )
    (net (code "251") (name "/HDR_T29") (class "Default")
      (node (ref "HDR_T") (pin "29") (pinfunction "29_29") (pintype "passive"))
    )
    (net (code "252") (name "/HDR_T30") (class "Default")
      (node (ref "HDR_T") (pin "30") (pinfunction "30_30") (pintype "passive"))
    )
    (net (code "253") (name "/HDR_T31") (class "Default")
      (node (ref "HDR_T") (pin "31") (pinfunction "31_31") (pintype "passive"))
    )
    (net (code "254") (name "/HDR_T32") (class "Default")
      (node (ref "HDR_T") (pin "32") (pinfunction "32_32") (pintype "passive"))
    )
    (net (code "255") (name "/HDR_T33") (class "Default")
      (node (ref "HDR_T") (pin "33") (pinfunction "33_33") (pintype "passive"))
    )
    (net (code "256") (name "/HDR_T35") (class "Default")
      (node (ref "HDR_T") (pin "35") (pinfunction "35_35") (pintype "passive"))
    )
    (net (code "257") (name "/HDR_T37") (class "Default")
      (node (ref "HDR_T") (pin "37") (pinfunction "37_37") (pintype "passive"))
    )
    (net (code "258") (name "/HDR_T39") (class "Default")
      (node (ref "HDR_T") (pin "39") (pinfunction "39_39") (pintype "passive"))
    )
    (net (code "259") (name "/HDR_T41") (class "Default")
      (node (ref "HDR_T") (pin "41") (pinfunction "41_41") (pintype "passive"))
    )
    (net (code "260") (name "/HDR_T43") (class "Default")
      (node (ref "HDR_T") (pin "43") (pinfunction "43_43") (pintype "passive"))
    )
    (net (code "261") (name "/HDR_T45") (class "Default")
      (node (ref "HDR_T") (pin "45") (pinfunction "45_45") (pintype "passive"))
    )
    (net (code "262") (name "/HDR_T47") (class "Default")
      (node (ref "HDR_T") (pin "47") (pinfunction "47_47") (pintype "passive"))
    )
    (net (code "263") (name "/HDR_T49") (class "Default")
      (node (ref "HDR_T") (pin "49") (pinfunction "49_49") (pintype "passive"))
    )
    (net (code "264") (name "/HDR_T51") (class "Default")
      (node (ref "HDR_T") (pin "51") (pinfunction "51_51") (pintype "passive"))
    )
    (net (code "265") (name "/HDR_T53") (class "Default")
      (node (ref "HDR_T") (pin "53") (pinfunction "53_53") (pintype "passive"))
    )
    (net (code "266") (name "/HDR_T55") (class "Default")
      (node (ref "HDR_T") (pin "55") (pinfunction "55_55") (pintype "passive"))
    )
    (net (code "267") (name "/HDR_T57") (class "Default")
      (node (ref "HDR_T") (pin "57") (pinfunction "57_57") (pintype "passive"))
    )
    (net (code "268") (name "/HDR_T59") (class "Default")
      (node (ref "HDR_T") (pin "59") (pinfunction "59_59") (pintype "passive"))
    )
    (net (code "269") (name "/HDR_T61") (class "Default")
      (node (ref "HDR_T") (pin "61") (pinfunction "61_61") (pintype "passive"))
    )
    (net (code "270") (name "/HDR_T63") (class "Default")
      (node (ref "HDR_T") (pin "63") (pinfunction "63_63") (pintype "passive"))
    )
    (net (code "271") (name "/HDR_T65") (class "Default")
      (node (ref "HDR_T") (pin "65") (pinfunction "65_65") (pintype "passive"))
    )
    (net (code "272") (name "/HDR_T67") (class "Default")
      (node (ref "HDR_T") (pin "67") (pinfunction "67_67") (pintype "passive"))
    )
    (net (code "273") (name "/HDR_T69") (class "Default")
      (node (ref "HDR_T") (pin "69") (pinfunction "69_69") (pintype "passive"))
    )
    (net (code "274") (name "/HDR_T71") (class "Default")
      (node (ref "HDR_T") (pin "71") (pinfunction "71_71") (pintype "passive"))
    )
    (net (code "275") (name "/HDR_T73") (class "Default")
      (node (ref "HDR_T") (pin "73") (pinfunction "73_73") (pintype "passive"))
    )
    (net (code "276") (name "/HDR_T75") (class "Default")
      (node (ref "HDR_T") (pin "75") (pinfunction "75_75") (pintype "passive"))
    )
    (net (code "277") (name "/HDR_T77") (class "Default")
      (node (ref "HDR_T") (pin "77") (pinfunction "77_77") (pintype "passive"))
    )
    (net (code "278") (name "/HDR_T79") (class "Default")
      (node (ref "HDR_T") (pin "79") (pinfunction "79_79") (pintype "passive"))
    )
    (net (code "279") (name "/HDR_T81") (class "Default")
      (node (ref "HDR_T") (pin "81") (pinfunction "81_81") (pintype "passive"))
    )
    (net (code "280") (name "/HDR_T83") (class "Default")
      (node (ref "HDR_T") (pin "83") (pinfunction "83_83") (pintype "passive"))
    )
    (net (code "281") (name "/HDR_T85") (class "Default")
      (node (ref "HDR_T") (pin "85") (pinfunction "85_85") (pintype "passive"))
    )
    (net (code "282") (name "/HDR_T87") (class "Default")
      (node (ref "HDR_T") (pin "87") (pinfunction "87_87") (pintype "passive"))
    )
    (net (code "283") (name "/HDR_T89") (class "Default")
      (node (ref "HDR_T") (pin "89") (pinfunction "89_89") (pintype "passive"))
    )
    (net (code "284") (name "/NEXUS_TCK") (class "Default")
      (node (ref "HDR_T") (pin "82") (pinfunction "82_82") (pintype "passive"))
    )
    (net (code "285") (name "/NEXUS_TDI") (class "Default")
      (node (ref "HDR_T") (pin "84") (pinfunction "84_84") (pintype "passive"))
    )
    (net (code "286") (name "/NEXUS_TDO") (class "Default")
      (node (ref "HDR_T") (pin "76") (pinfunction "76_76") (pintype "passive"))
    )
    (net (code "287") (name "/NEXUS_TMS") (class "Default")
      (node (ref "HDR_T") (pin "80") (pinfunction "80_80") (pintype "passive"))
    )
    (net (code "288") (name "/ONE_WIRE_DBID") (class "Default")
      (node (ref "HDR_T") (pin "92") (pinfunction "92_92") (pintype "passive"))
      (node (ref "R2") (pin "1") (pinfunction "1_1") (pintype "passive"))
    )
    (net (code "289") (name "/REF_CLK") (class "Default")
      (node (ref "HDR_B") (pin "4") (pinfunction "4_4") (pintype "passive"))
    )
    (net (code "290") (name "/VCCX_REF") (class "Default")
      (node (ref "HDR_T") (pin "91") (pinfunction "91_91") (pintype "passive"))
    )
    (net (code "297") (name "3V3") (class "Default")
      (node (ref "R2") (pin "2") (pinfunction "2_2") (pintype "passive"))
      (node (ref "R3") (pin "1") (pinfunction "1_1") (pintype "passive"))
    )
    (net (code "298") (name "GND") (class "Default")
      (node (ref "HDR_B") (pin "1") (pinfunction "1_1") (pintype "passive"))
      (node (ref "HDR_B") (pin "100") (pinfunction "100_100") (pintype "passive"))
      (node (ref "HDR_B") (pin "98") (pinfunction "98_98") (pintype "passive"))
      (node (ref "HDR_B") (pin "MH1") (pinfunction "MH1_MH1") (pintype "passive"))
      (node (ref "HDR_B") (pin "MH2") (pinfunction "MH2_MH2") (pintype "passive"))
      (node (ref "HDR_B") (pin "MH3") (pinfunction "MH3_MH3") (pintype "passive"))
      (node (ref "HDR_B") (pin "MH4") (pinfunction "MH4_MH4") (pintype "passive"))
      (node (ref "HDR_L") (pin "MH1") (pinfunction "MH1_MH1") (pintype "passive"))
      (node (ref "HDR_L") (pin "MH2") (pinfunction "MH2_MH2") (pintype "passive"))
      (node (ref "HDR_L") (pin "MH3") (pinfunction "MH3_MH3") (pintype "passive"))
      (node (ref "HDR_L") (pin "MH4") (pinfunction "MH4_MH4") (pintype "passive"))
      (node (ref "HDR_T") (pin "1") (pinfunction "1_1") (pintype "passive"))
      (node (ref "HDR_T") (pin "100") (pinfunction "100_100") (pintype "passive"))
      (node (ref "HDR_T") (pin "98") (pinfunction "98_98") (pintype "passive"))
      (node (ref "HDR_T") (pin "MH1") (pinfunction "MH1_MH1") (pintype "passive"))
      (node (ref "HDR_T") (pin "MH2") (pinfunction "MH2_MH2") (pintype "passive"))
      (node (ref "HDR_T") (pin "MH3") (pinfunction "MH3_MH3") (pintype "passive"))
      (node (ref "HDR_T") (pin "MH4") (pinfunction "MH4_MH4") (pintype "passive"))
      (node (ref "R1") (pin "2") (pinfunction "2_2") (pintype "passive"))
    )
    (net (code "299") (name "Net-(HDR_B-Pad94)") (class "Default")
      (node (ref "HDR_B") (pin "94") (pinfunction "94_94") (pintype "passive"))
      (node (ref "HDR_B") (pin "96") (pinfunction "96_96") (pintype "passive"))
      (node (ref "HDR_T") (pin "94") (pinfunction "94_94") (pintype "passive"))
      (node (ref "HDR_T") (pin "96") (pinfunction "96_96") (pintype "passive"))
    )
    (net (code "300") (name "Net-(HDR_B-Pad97)") (class "Default")
      (node (ref "HDR_B") (pin "97") (pinfunction "97_97") (pintype "passive"))
      (node (ref "HDR_B") (pin "99") (pinfunction "99_99") (pintype "passive"))
      (node (ref "HDR_T") (pin "97") (pinfunction "97_97") (pintype "passive"))
      (node (ref "HDR_T") (pin "99") (pinfunction "99_99") (pintype "passive"))
    )
    (net (code "301") (name "VCCX") (class "Default")
      (node (ref "HDR_B") (pin "93") (pinfunction "93_93") (pintype "passive"))
      (node (ref "HDR_B") (pin "95") (pinfunction "95_95") (pintype "passive"))
      (node (ref "HDR_T") (pin "93") (pinfunction "93_93") (pintype "passive"))
      (node (ref "HDR_T") (pin "95") (pinfunction "95_95") (pintype "passive"))
    )
  )
)
